# WiFi_BLE2.net
KiCad netlist of a schematic drawn in Altium Designer
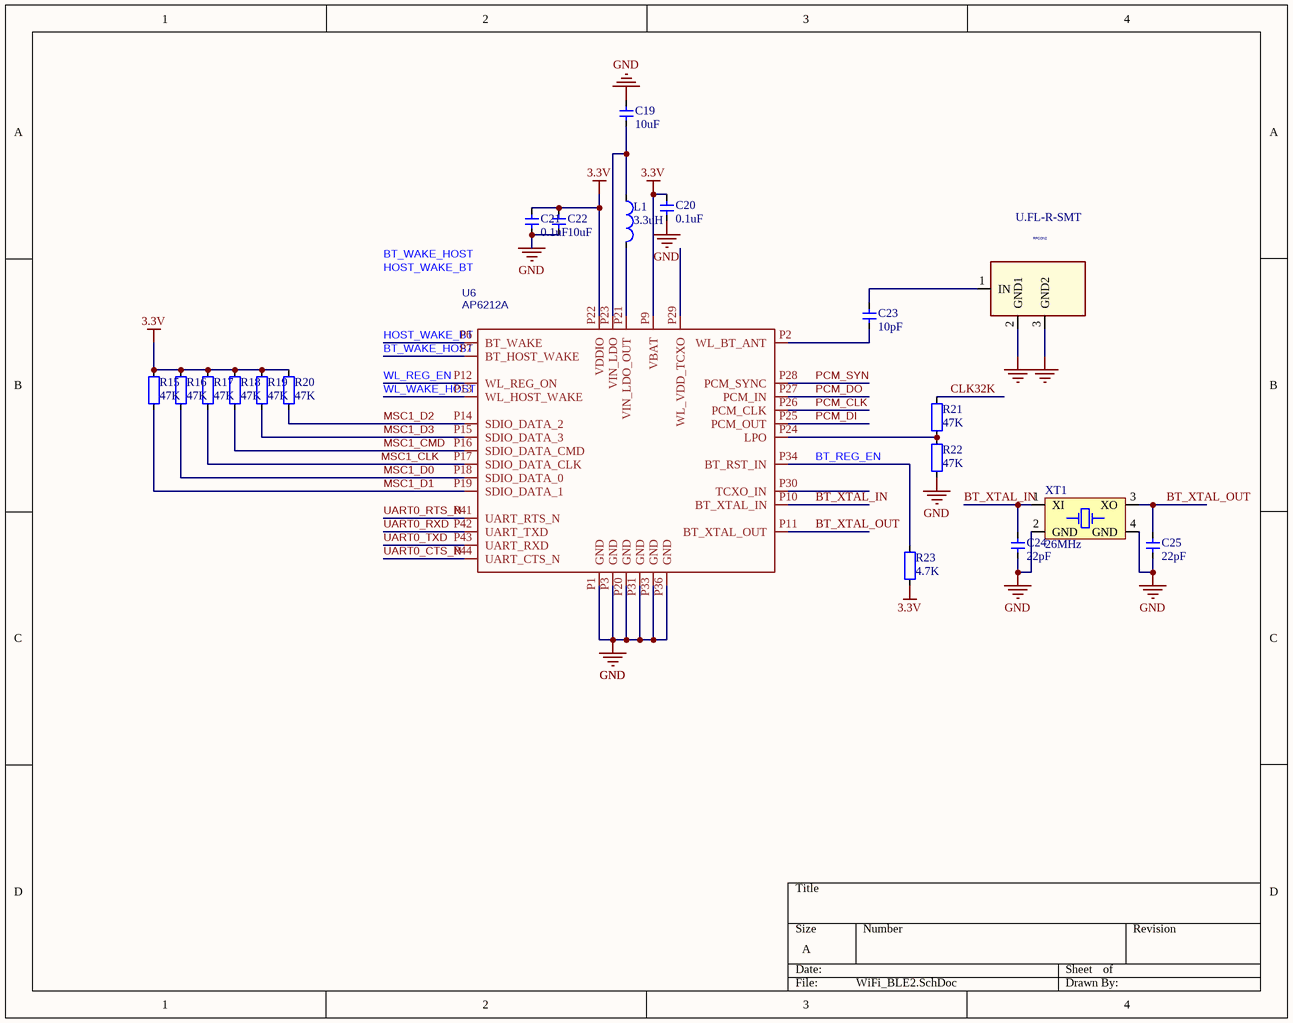
[diagram p0: WiFi_BLE2.SchDoc]

(export (version "E")
  (design (tool "Eeschema 10.0.6"))
  (components
    (comp (ref "C19")
      (value "10uF")
      (footprint "PCB_PassiveCap:CAP_0805")
      (description "Capacitor")
      (fields (field (name "Comment") "Cap_0805"))
      (libsource (lib "SCH_Passive") (part "Cap_0805"))
    )
    (comp (ref "C20")
      (value "0.1uF")
      (footprint "PCB_PassiveCap:CAP_0402")
      (description "Capacitor")
      (fields (field (name "Comment") "Cap_0402"))
      (libsource (lib "SCH_Passive") (part "Cap_0402"))
    )
    (comp (ref "C21")
      (value "0.1uF")
      (footprint "PCB_PassiveCap:CAP_0402")
      (description "Capacitor")
      (fields (field (name "Comment") "Cap_0402"))
      (libsource (lib "SCH_Passive") (part "Cap_0402"))
    )
    (comp (ref "C22")
      (value "10uF")
      (footprint "PCB_PassiveCap:CAP_0805")
      (description "Capacitor")
      (fields (field (name "Comment") "Cap_0805"))
      (libsource (lib "SCH_Passive") (part "Cap_0805"))
    )
    (comp (ref "C23")
      (value "10pF")
      (footprint "PCB_PassiveCap:CAP_0402")
      (description "Capacitor")
      (fields (field (name "Comment") "Cap_0402"))
      (libsource (lib "SCH_Passive") (part "Cap_0402"))
    )
    (comp (ref "C24")
      (value "22pF")
      (footprint "PCB_PassiveCap:CAP_0402")
      (description "Capacitor")
      (fields (field (name "Comment") "Cap_0402"))
      (libsource (lib "SCH_Passive") (part "Cap_0402"))
    )
    (comp (ref "C25")
      (value "22pF")
      (footprint "PCB_PassiveCap:CAP_0402")
      (description "Capacitor")
      (fields (field (name "Comment") "Cap_0402"))
      (libsource (lib "SCH_Passive") (part "Cap_0402"))
    )
    (comp (ref "L1")
      (value "3.3uH")
      (footprint "PCB_PassiveInd:IND_0402")
      (description "Inductor")
      (fields (field (name "Comment") "Ind_0402"))
      (libsource (lib "SCH_Passive") (part "Ind_0402"))
    )
    (comp (ref "R15")
      (value "47K")
      (footprint "PCB_PassiveRes:RES_0402")
      (description "Resistor")
      (fields (field (name "Comment") "Res_0402"))
      (libsource (lib "SCH_Passive") (part "Res_0402"))
    )
    (comp (ref "R16")
      (value "47K")
      (footprint "PCB_PassiveRes:RES_0402")
      (description "Resistor")
      (fields (field (name "Comment") "Res_0402"))
      (libsource (lib "SCH_Passive") (part "Res_0402"))
    )
    (comp (ref "R17")
      (value "47K")
      (footprint "PCB_PassiveRes:RES_0402")
      (description "Resistor")
      (fields (field (name "Comment") "Res_0402"))
      (libsource (lib "SCH_Passive") (part "Res_0402"))
    )
    (comp (ref "R18")
      (value "47K")
      (footprint "PCB_PassiveRes:RES_0402")
      (description "Resistor")
      (fields (field (name "Comment") "Res_0402"))
      (libsource (lib "SCH_Passive") (part "Res_0402"))
    )
    (comp (ref "R19")
      (value "47K")
      (footprint "PCB_PassiveRes:RES_0402")
      (description "Resistor")
      (fields (field (name "Comment") "Res_0402"))
      (libsource (lib "SCH_Passive") (part "Res_0402"))
    )
    (comp (ref "R20")
      (value "47K")
      (footprint "PCB_PassiveRes:RES_0402")
      (description "Resistor")
      (fields (field (name "Comment") "Res_0402"))
      (libsource (lib "SCH_Passive") (part "Res_0402"))
    )
    (comp (ref "R21")
      (value "47K")
      (footprint "PCB_PassiveRes:RES_0402")
      (description "Resistor")
      (fields (field (name "Comment") "Res_0402"))
      (libsource (lib "SCH_Passive") (part "Res_0402"))
    )
    (comp (ref "R22")
      (value "47K")
      (footprint "PCB_PassiveRes:RES_0402")
      (description "Resistor")
      (fields (field (name "Comment") "Res_0402"))
      (libsource (lib "SCH_Passive") (part "Res_0402"))
    )
    (comp (ref "R23")
      (value "4.7K")
      (footprint "PCB_PassiveRes:RES_0402")
      (description "Resistor")
      (fields (field (name "Comment") "Res_0402"))
      (libsource (lib "SCH_Passive") (part "Res_0402"))
    )
    (comp (ref "RFCON2")
      (value "U.FL-R-SMT")
      (footprint "ANTENNA_DN007N")
      (libsource (lib "*") (part "ANT_0"))
    )
    (comp (ref "U6")
      (value "AP6212A")
      (footprint "AP6210")
      (fields (field (name "BOM_MANUFACTURER PART") "?"))
      (libsource (lib "altium-import") (part "root_0_AP6210_"))
    )
    (comp (ref "XT1")
      (value "26MHz")
      (footprint "PCB_Oscillator:XT_3225_4")
      (description "Crystal Oscillator")
      (fields (field (name "Comment") "XTAL_3225_4P"))
      (libsource (lib "SCH_Oscillator") (part "XTAL_3225_4P"))
    )
  )
  (nets
    (net (code "1") (name "/BT_REG_EN") (class "Default")
      (node (ref "R23") (pin "2") (pinfunction "2_2") (pintype "passive"))
      (node (ref "U6") (pin "P34") (pinfunction "BT_RST_IN_P34") (pintype "passive"))
    )
    (net (code "2") (name "/BT_WAKE_HOST") (class "Default")
      (node (ref "U6") (pin "P7") (pinfunction "BT_HOST_WAKE_P7") (pintype "passive"))
    )
    (net (code "3") (name "/BT_XTAL_IN") (class "Default")
      (node (ref "C24") (pin "2") (pinfunction "2_2") (pintype "passive"))
      (node (ref "U6") (pin "P10") (pinfunction "BT_XTAL_IN_P10") (pintype "passive"))
      (node (ref "XT1") (pin "1") (pinfunction "XI_1") (pintype "passive"))
    )
    (net (code "4") (name "/BT_XTAL_OUT") (class "Default")
      (node (ref "C25") (pin "2") (pinfunction "2_2") (pintype "passive"))
      (node (ref "U6") (pin "P11") (pinfunction "BT_XTAL_OUT_P11") (pintype "passive"))
      (node (ref "XT1") (pin "3") (pinfunction "XO_3") (pintype "passive"))
    )
    (net (code "5") (name "/CLK32K") (class "Default")
      (node (ref "R21") (pin "2") (pinfunction "2_2") (pintype "passive"))
    )
    (net (code "6") (name "/HOST_WAKE_BT") (class "Default")
      (node (ref "U6") (pin "P6") (pinfunction "BT_WAKE_P6") (pintype "passive"))
    )
    (net (code "7") (name "/MSC1_CLK") (class "Default")
      (node (ref "R17") (pin "1") (pinfunction "1_1") (pintype "passive"))
      (node (ref "U6") (pin "P17") (pinfunction "SDIO_DATA_CLK_P17") (pintype "passive"))
    )
    (net (code "8") (name "/MSC1_CMD") (class "Default")
      (node (ref "R18") (pin "1") (pinfunction "1_1") (pintype "passive"))
      (node (ref "U6") (pin "P16") (pinfunction "SDIO_DATA_CMD_P16") (pintype "passive"))
    )
    (net (code "9") (name "/MSC1_D0") (class "Default")
      (node (ref "R16") (pin "1") (pinfunction "1_1") (pintype "passive"))
      (node (ref "U6") (pin "P18") (pinfunction "SDIO_DATA_0_P18") (pintype "passive"))
    )
    (net (code "10") (name "/MSC1_D1") (class "Default")
      (node (ref "R15") (pin "1") (pinfunction "1_1") (pintype "passive"))
      (node (ref "U6") (pin "P19") (pinfunction "SDIO_DATA_1_P19") (pintype "passive"))
    )
    (net (code "11") (name "/MSC1_D2") (class "Default")
      (node (ref "R20") (pin "1") (pinfunction "1_1") (pintype "passive"))
      (node (ref "U6") (pin "P14") (pinfunction "SDIO_DATA_2_P14") (pintype "passive"))
    )
    (net (code "12") (name "/MSC1_D3") (class "Default")
      (node (ref "R19") (pin "1") (pinfunction "1_1") (pintype "passive"))
      (node (ref "U6") (pin "P15") (pinfunction "SDIO_DATA_3_P15") (pintype "passive"))
    )
    (net (code "13") (name "/PCM_CLK") (class "Default")
      (node (ref "U6") (pin "P26") (pinfunction "PCM_CLK_P26") (pintype "passive"))
    )
    (net (code "14") (name "/PCM_DI") (class "Default")
      (node (ref "U6") (pin "P25") (pinfunction "PCM_OUT_P25") (pintype "passive"))
    )
    (net (code "15") (name "/PCM_DO") (class "Default")
      (node (ref "U6") (pin "P27") (pinfunction "PCM_IN_P27") (pintype "passive"))
    )
    (net (code "16") (name "/PCM_SYN") (class "Default")
      (node (ref "U6") (pin "P28") (pinfunction "PCM_SYNC_P28") (pintype "passive"))
    )
    (net (code "17") (name "/UART0_CTS_N") (class "Default")
      (node (ref "U6") (pin "P44") (pinfunction "UART_CTS_N_P44") (pintype "passive"))
    )
    (net (code "18") (name "/UART0_RTS_N") (class "Default")
      (node (ref "U6") (pin "P41") (pinfunction "UART_RTS_N_P41") (pintype "passive"))
    )
    (net (code "19") (name "/UART0_RXD") (class "Default")
      (node (ref "U6") (pin "P42") (pinfunction "UART_TXD_P42") (pintype "passive"))
    )
    (net (code "20") (name "/UART0_TXD") (class "Default")
      (node (ref "U6") (pin "P43") (pinfunction "UART_RXD_P43") (pintype "passive"))
    )
    (net (code "21") (name "/WL_REG_EN") (class "Default")
      (node (ref "U6") (pin "P12") (pinfunction "WL_REG_ON_P12") (pintype "passive"))
    )
    (net (code "22") (name "/WL_WAKE_HOST") (class "Default")
      (node (ref "U6") (pin "P13") (pinfunction "WL_HOST_WAKE_P13") (pintype "passive"))
    )
    (net (code "23") (name "3.3V") (class "Default")
      (node (ref "C20") (pin "2") (pinfunction "2_2") (pintype "passive"))
      (node (ref "C21") (pin "2") (pinfunction "2_2") (pintype "passive"))
      (node (ref "C22") (pin "2") (pinfunction "2_2") (pintype "passive"))
      (node (ref "R15") (pin "2") (pinfunction "2_2") (pintype "passive"))
      (node (ref "R16") (pin "2") (pinfunction "2_2") (pintype "passive"))
      (node (ref "R17") (pin "2") (pinfunction "2_2") (pintype "passive"))
      (node (ref "R18") (pin "2") (pinfunction "2_2") (pintype "passive"))
      (node (ref "R19") (pin "2") (pinfunction "2_2") (pintype "passive"))
      (node (ref "R20") (pin "2") (pinfunction "2_2") (pintype "passive"))
      (node (ref "R23") (pin "1") (pinfunction "1_1") (pintype "passive"))
      (node (ref "U6") (pin "P22") (pinfunction "VDDIO_P22") (pintype "passive"))
      (node (ref "U6") (pin "P9") (pinfunction "VBAT_P9") (pintype "passive"))
    )
    (net (code "24") (name "GND") (class "Default")
      (node (ref "C19") (pin "2") (pinfunction "2_2") (pintype "passive"))
      (node (ref "C20") (pin "1") (pinfunction "1_1") (pintype "passive"))
      (node (ref "C21") (pin "1") (pinfunction "1_1") (pintype "passive"))
      (node (ref "C22") (pin "1") (pinfunction "1_1") (pintype "passive"))
      (node (ref "C24") (pin "1") (pinfunction "1_1") (pintype "passive"))
      (node (ref "C25") (pin "1") (pinfunction "1_1") (pintype "passive"))
      (node (ref "R22") (pin "1") (pinfunction "1_1") (pintype "passive"))
      (node (ref "RFCON2") (pin "2") (pinfunction "GND1_2") (pintype "passive"))
      (node (ref "RFCON2") (pin "3") (pinfunction "GND2_3") (pintype "passive"))
      (node (ref "U6") (pin "P1") (pinfunction "GND_P1") (pintype "passive"))
      (node (ref "U6") (pin "P20") (pinfunction "GND_P20") (pintype "passive"))
      (node (ref "U6") (pin "P3") (pinfunction "GND_P3") (pintype "passive"))
      (node (ref "U6") (pin "P31") (pinfunction "GND_P31") (pintype "passive"))
      (node (ref "U6") (pin "P33") (pinfunction "GND_P33") (pintype "passive"))
      (node (ref "U6") (pin "P36") (pinfunction "GND_P36") (pintype "passive"))
      (node (ref "XT1") (pin "2") (pinfunction "GND_2") (pintype "passive"))
      (node (ref "XT1") (pin "4") (pinfunction "GND_4") (pintype "passive"))
    )
    (net (code "25") (name "Net-(RFCON2-IN)") (class "Default")
      (node (ref "C23") (pin "2") (pinfunction "2_2") (pintype "passive"))
      (node (ref "RFCON2") (pin "1") (pinfunction "IN_1") (pintype "passive"))
    )
    (net (code "26") (name "Net-(U6-LPO)") (class "Default")
      (node (ref "R21") (pin "1") (pinfunction "1_1") (pintype "passive"))
      (node (ref "R22") (pin "2") (pinfunction "2_2") (pintype "passive"))
      (node (ref "U6") (pin "P24") (pinfunction "LPO_P24") (pintype "passive"))
    )
    (net (code "27") (name "Net-(U6-VIN_LDO)") (class "Default")
      (node (ref "C19") (pin "1") (pinfunction "1_1") (pintype "passive"))
      (node (ref "L1") (pin "1") (pinfunction "1_1") (pintype "passive"))
      (node (ref "U6") (pin "P23") (pinfunction "VIN_LDO_P23") (pintype "passive"))
    )
    (net (code "28") (name "Net-(U6-VIN_LDO_OUT)") (class "Default")
      (node (ref "L1") (pin "2") (pinfunction "2_2") (pintype "passive"))
      (node (ref "U6") (pin "P21") (pinfunction "VIN_LDO_OUT_P21") (pintype "passive"))
    )
    (net (code "29") (name "Net-(U6-WL_BT_ANT)") (class "Default")
      (node (ref "C23") (pin "1") (pinfunction "1_1") (pintype "passive"))
      (node (ref "U6") (pin "P2") (pinfunction "WL_BT_ANT_P2") (pintype "passive"))
    )
    (net (code "30") (name "unconnected-(U6-TCXO_IN-PadP30)") (class "Default")
      (node (ref "U6") (pin "P30") (pinfunction "TCXO_IN_P30") (pintype "passive"))
    )
    (net (code "31") (name "unconnected-(U6-WL_VDD_TCXO-PadP29)") (class "Default")
      (node (ref "U6") (pin "P29") (pinfunction "WL_VDD_TCXO_P29") (pintype "passive"))
    )
  )
)
